# IP_12081213.net
KiCad netlist of a schematic drawn in Altium Designer
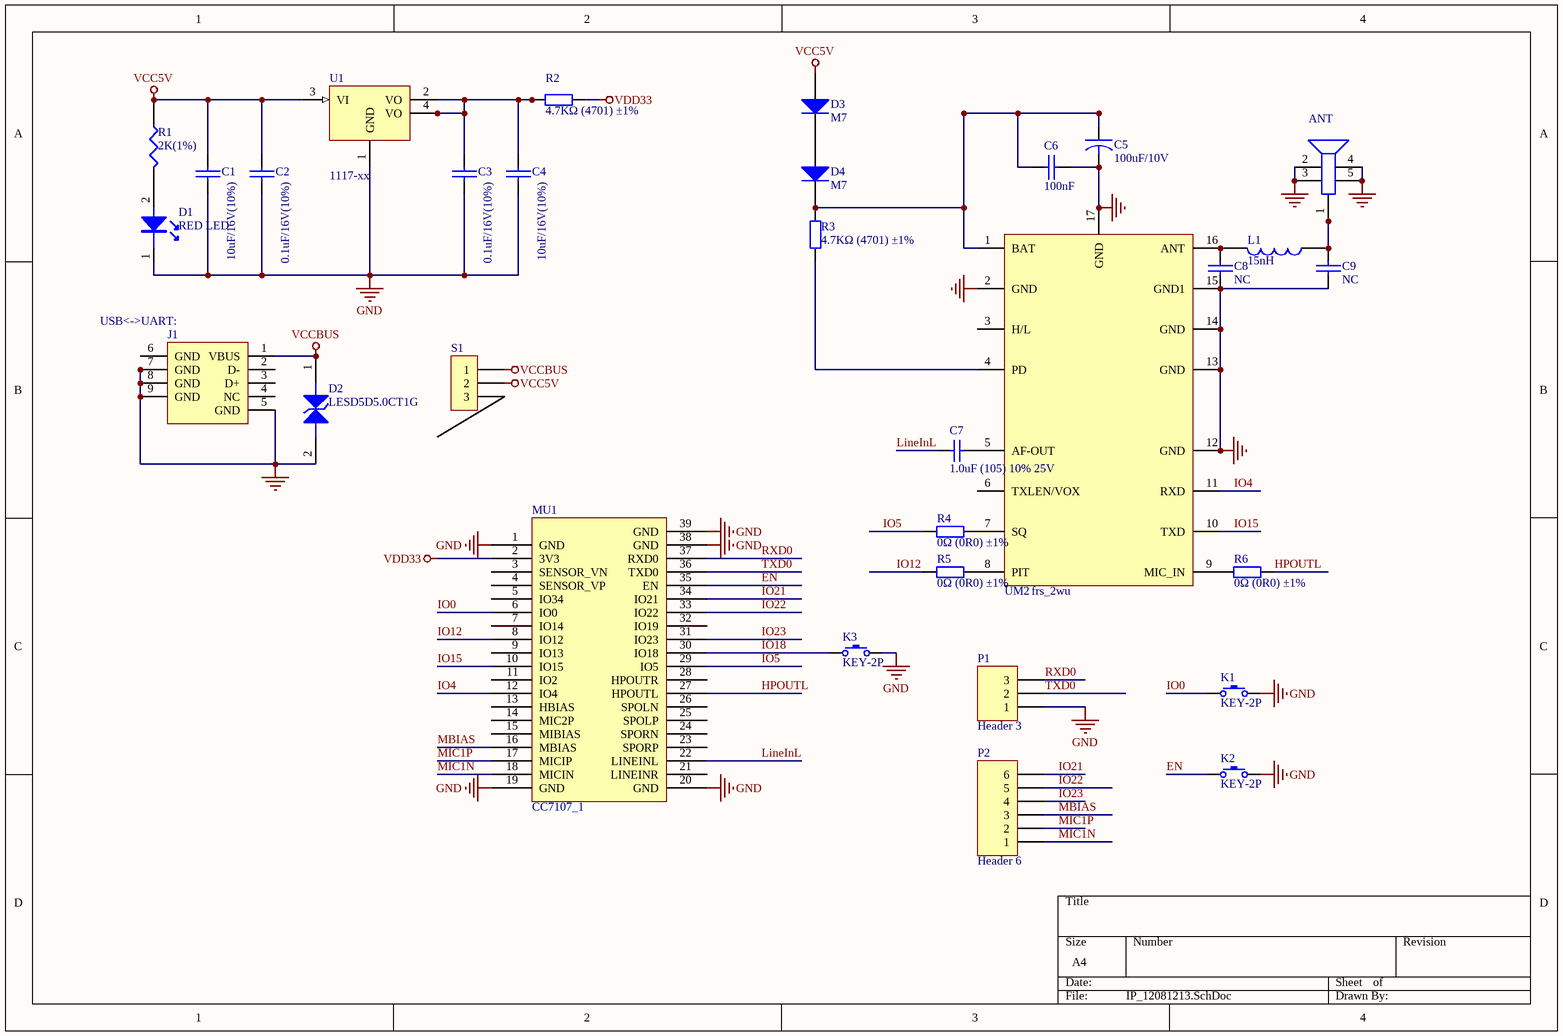
[diagram p0: IP_12081213.SchDoc]

(export (version "E")
  (design (tool "Eeschema 10.0.6"))
  (components
    (comp (ref "ANT")
      (value "~")
      (footprint "SMA-kHD信号输入头长 5.1宽5.1 5脚")
      (libsource (lib "*") (part "SPEAKER1"))
    )
    (comp (ref "C1")
      (value "10uF/16V(10%)")
      (footprint "LC-0603_C")
      (description "Capacitor")
      (libsource (lib "*") (part "CAP"))
    )
    (comp (ref "C2")
      (value "0.1uF/16V(10%)")
      (footprint "LC-0402_C")
      (description "Capacitor")
      (libsource (lib "*") (part "CAP"))
    )
    (comp (ref "C3")
      (value "0.1uF/16V(10%)")
      (footprint "LC-0402_C")
      (description "Capacitor")
      (libsource (lib "*") (part "CAP"))
    )
    (comp (ref "C4")
      (value "10uF/16V(10%)")
      (footprint "LC-0603_C")
      (description "Capacitor")
      (libsource (lib "*") (part "CAP"))
    )
    (comp (ref "C5")
      (value "100uF/10V")
      (footprint "3216")
      (description "Capacitor")
      (libsource (lib "*") (part "CAPACITOR"))
    )
    (comp (ref "C6")
      (value "100nF")
      (footprint "LC-0402_C")
      (description "Capacitor")
      (libsource (lib "*") (part "CAP"))
    )
    (comp (ref "C7")
      (value "1.0uF (105) 10% 25V")
      (footprint "LC-0402_C")
      (description "贴片电容")
      (libsource (lib "Miscellaneous Devices LC") (part "0402 1.0uF (105) 10% 25V"))
    )
    (comp (ref "C8")
      (value "NC")
      (footprint "LC-0402_C")
      (description "Capacitor")
      (libsource (lib "*") (part "CAP"))
    )
    (comp (ref "C9")
      (value "NC")
      (footprint "LC-0402_C")
      (description "Capacitor")
      (libsource (lib "*") (part "CAP"))
    )
    (comp (ref "D1")
      (value "RED LED")
      (footprint "LED5MM 2.6 6")
      (description "LED, SMD, GREEN, 3x2.2mm")
      (libsource (lib "*") (part "LEDA"))
    )
    (comp (ref "D2")
      (value "LESD5D5.0CT1G")
      (footprint "LC-SOD-523")
      (description "Zener Diode")
      (libsource (lib "*") (part "LESD5D5.0CT1G"))
    )
    (comp (ref "D3")
      (value "M7")
      (footprint "SMA")
      (description "二极管")
      (libsource (lib "Miscellaneous Devices LC") (part "SMA(DO-214AC) M7"))
    )
    (comp (ref "D4")
      (value "M7")
      (footprint "SMA")
      (description "二极管")
      (libsource (lib "Miscellaneous Devices LC") (part "SMA(DO-214AC) M7"))
    )
    (comp (ref "J1")
      (value "~")
      (footprint "USB MICRO5P/F B型牛角 - 3D")
      (libsource (lib "*") (part "USB_CON8"))
    )
    (comp (ref "K1")
      (value "KEY-2P")
      (footprint "key - 1")
      (description "Key")
      (libsource (lib "General") (part "KEY-2P"))
    )
    (comp (ref "K2")
      (value "KEY-2P")
      (footprint "key - 1")
      (description "Key")
      (libsource (lib "General") (part "KEY-2P"))
    )
    (comp (ref "K3")
      (value "KEY-2P")
      (footprint "KE卧式带支架 6*6*4.3/5/6/7/8/9.5 2脚侧按微动")
      (description "Key")
      (libsource (lib "General") (part "KEY-2P"))
    )
    (comp (ref "L1") (value "15nH") (footprint "LC-1206_L") (libsource (lib "*") (part "INDUCTOR")))
    (comp (ref "MU1")
      (value "CC7107_1")
      (footprint "ESP32-A1S")
      (libsource (lib "SchLibl") (part "CC7107_1"))
    )
    (comp (ref "P1")
      (value "Header 3")
      (footprint "HDR1X3")
      (description "Header, 3-Pin")
      (fields (field (name "PUBLISHER") "Altium Limited"))
      (libsource (lib "Miscellaneous Connectors") (part "Header 3"))
    )
    (comp (ref "P2")
      (value "Header 6")
      (footprint "HDR1X6")
      (description "Header, 6-Pin")
      (fields (field (name "PUBLISHER") "Altium Limited"))
      (libsource (lib "Miscellaneous Connectors") (part "Header 6"))
    )
    (comp (ref "R1") (value "2K(1%)") (footprint "LC-0402_R") (libsource (lib "*") (part "RES1")))
    (comp (ref "R2")
      (value "4.7KΩ (4701) ±1%")
      (footprint "LC-0402_R")
      (description "贴片电阻")
      (libsource (lib "") (part "0402 4.7KΩ (4701) 1%_1"))
    )
    (comp (ref "R3")
      (value "4.7KΩ (4701) ±1%")
      (footprint "LC-0402_R")
      (description "贴片电阻")
      (libsource (lib "Miscellaneous Devices LC") (part "0402 4.7KΩ (4701) 1%"))
    )
    (comp (ref "R4")
      (value "0Ω (0R0) ±1%")
      (footprint "LC-0402_R")
      (description "贴片电阻")
      (libsource (lib "Miscellaneous Devices LC") (part "0402 0Ω (0R0) 1%"))
    )
    (comp (ref "R5")
      (value "0Ω (0R0) ±1%")
      (footprint "LC-0402_R")
      (description "贴片电阻")
      (libsource (lib "Miscellaneous Devices LC") (part "0402 0Ω (0R0) 1%"))
    )
    (comp (ref "R6")
      (value "0Ω (0R0) ±1%")
      (footprint "LC-0402_R")
      (description "贴片电阻")
      (libsource (lib "Miscellaneous Devices LC") (part "0402 0Ω (0R0) 1%"))
    )
    (comp (ref "S1")
      (value "~")
      (footprint "K 两档开关SS-21D00")
      (description "Connector")
      (libsource (lib "*") (part "CON3"))
    )
    (comp (ref "U1")
      (value "1117-xx")
      (footprint "SOT223 LM1117")
      (description "Linear Regulator")
      (libsource (lib "General") (part "1117"))
    )
    (comp (ref "UM2") (value "frs_2wu") (footprint "模块HKT-82-VER02") (libsource (lib "*") (part "IC")))
  )
  (nets
    (net (code "1") (name "/EN") (class "Default")
      (node (ref "K2") (pin "1") (pinfunction "1_1") (pintype "passive"))
      (node (ref "MU1") (pin "35") (pinfunction "EN_35") (pintype "passive"))
    )
    (net (code "2") (name "/HPOUTL") (class "Default")
      (node (ref "MU1") (pin "27") (pinfunction "HPOUTL_27") (pintype "passive"))
      (node (ref "R6") (pin "2") (pinfunction "2_2") (pintype "passive"))
    )
    (net (code "3") (name "/IO0") (class "Default")
      (node (ref "K1") (pin "1") (pinfunction "1_1") (pintype "passive"))
      (node (ref "MU1") (pin "6") (pinfunction "IO0_6") (pintype "passive"))
    )
    (net (code "4") (name "/IO4") (class "Default")
      (node (ref "MU1") (pin "12") (pinfunction "IO4_12") (pintype "passive"))
      (node (ref "UM2") (pin "11") (pinfunction "RXD_11") (pintype "passive"))
    )
    (net (code "5") (name "/IO5") (class "Default")
      (node (ref "MU1") (pin "29") (pinfunction "IO5_29") (pintype "passive"))
      (node (ref "R4") (pin "1") (pinfunction "1_1") (pintype "passive"))
    )
    (net (code "6") (name "/IO12") (class "Default")
      (node (ref "MU1") (pin "8") (pinfunction "IO12_8") (pintype "passive"))
      (node (ref "R5") (pin "1") (pinfunction "1_1") (pintype "passive"))
    )
    (net (code "7") (name "/IO15") (class "Default")
      (node (ref "MU1") (pin "10") (pinfunction "IO15_10") (pintype "passive"))
      (node (ref "UM2") (pin "10") (pinfunction "TXD_10") (pintype "passive"))
    )
    (net (code "8") (name "/IO18") (class "Default")
      (node (ref "K3") (pin "1") (pinfunction "1_1") (pintype "passive"))
      (node (ref "MU1") (pin "30") (pinfunction "IO18_30") (pintype "passive"))
    )
    (net (code "9") (name "/IO21") (class "Default")
      (node (ref "MU1") (pin "34") (pinfunction "IO21_34") (pintype "passive"))
      (node (ref "P2") (pin "6") (pinfunction "6_6") (pintype "passive"))
    )
    (net (code "10") (name "/IO22") (class "Default")
      (node (ref "MU1") (pin "33") (pinfunction "IO22_33") (pintype "passive"))
      (node (ref "P2") (pin "5") (pinfunction "5_5") (pintype "passive"))
    )
    (net (code "11") (name "/IO23") (class "Default")
      (node (ref "MU1") (pin "31") (pinfunction "IO23_31") (pintype "passive"))
      (node (ref "P2") (pin "4") (pinfunction "4_4") (pintype "passive"))
    )
    (net (code "12") (name "/LineInL") (class "Default")
      (node (ref "C7") (pin "1") (pinfunction "1_1") (pintype "passive"))
      (node (ref "MU1") (pin "22") (pinfunction "LINEINL_22") (pintype "passive"))
    )
    (net (code "13") (name "/MBIAS") (class "Default")
      (node (ref "MU1") (pin "16") (pinfunction "MBIAS_16") (pintype "passive"))
      (node (ref "P2") (pin "3") (pinfunction "3_3") (pintype "passive"))
    )
    (net (code "14") (name "/MIC1N") (class "Default")
      (node (ref "MU1") (pin "18") (pinfunction "MICIN_18") (pintype "passive"))
      (node (ref "P2") (pin "1") (pinfunction "1_1") (pintype "passive"))
    )
    (net (code "15") (name "/MIC1P") (class "Default")
      (node (ref "MU1") (pin "17") (pinfunction "MICIP_17") (pintype "passive"))
      (node (ref "P2") (pin "2") (pinfunction "2_2") (pintype "passive"))
    )
    (net (code "16") (name "/RXD0") (class "Default")
      (node (ref "MU1") (pin "37") (pinfunction "RXD0_37") (pintype "passive"))
      (node (ref "P1") (pin "3") (pinfunction "3_3") (pintype "passive"))
    )
    (net (code "17") (name "/TXD0") (class "Default")
      (node (ref "MU1") (pin "36") (pinfunction "TXD0_36") (pintype "passive"))
      (node (ref "P1") (pin "2") (pinfunction "2_2") (pintype "passive"))
    )
    (net (code "18") (name "GND") (class "Default")
      (node (ref "ANT") (pin "2") (pinfunction "2_2") (pintype "passive"))
      (node (ref "ANT") (pin "3") (pinfunction "3_3") (pintype "passive"))
      (node (ref "ANT") (pin "4") (pinfunction "4_4") (pintype "passive"))
      (node (ref "ANT") (pin "5") (pinfunction "5_5") (pintype "passive"))
      (node (ref "C1") (pin "2") (pinfunction "2_2") (pintype "passive"))
      (node (ref "C2") (pin "2") (pinfunction "2_2") (pintype "passive"))
      (node (ref "C3") (pin "2") (pinfunction "2_2") (pintype "passive"))
      (node (ref "C4") (pin "2") (pinfunction "2_2") (pintype "passive"))
      (node (ref "C5") (pin "2") (pinfunction "2_2") (pintype "passive"))
      (node (ref "C6") (pin "2") (pinfunction "2_2") (pintype "passive"))
      (node (ref "C8") (pin "2") (pinfunction "2_2") (pintype "passive"))
      (node (ref "C9") (pin "2") (pinfunction "2_2") (pintype "passive"))
      (node (ref "D1") (pin "1") (pinfunction "C_1") (pintype "passive"))
      (node (ref "D2") (pin "2") (pinfunction "K_2") (pintype "passive"))
      (node (ref "J1") (pin "5") (pinfunction "GND_5") (pintype "passive"))
      (node (ref "J1") (pin "7") (pinfunction "GND_7") (pintype "passive"))
      (node (ref "J1") (pin "8") (pinfunction "GND_8") (pintype "passive"))
      (node (ref "J1") (pin "9") (pinfunction "GND_9") (pintype "passive"))
      (node (ref "K1") (pin "2") (pinfunction "2_2") (pintype "passive"))
      (node (ref "K2") (pin "2") (pinfunction "2_2") (pintype "passive"))
      (node (ref "K3") (pin "2") (pinfunction "2_2") (pintype "passive"))
      (node (ref "MU1") (pin "1") (pinfunction "GND_1") (pintype "passive"))
      (node (ref "MU1") (pin "19") (pinfunction "GND_19") (pintype "passive"))
      (node (ref "MU1") (pin "20") (pinfunction "GND_20") (pintype "passive"))
      (node (ref "MU1") (pin "38") (pinfunction "GND_38") (pintype "passive"))
      (node (ref "MU1") (pin "39") (pinfunction "GND_39") (pintype "passive"))
      (node (ref "P1") (pin "1") (pinfunction "1_1") (pintype "passive"))
      (node (ref "U1") (pin "1") (pinfunction "GND_1") (pintype "power_in"))
      (node (ref "UM2") (pin "12") (pinfunction "GND_12") (pintype "passive"))
      (node (ref "UM2") (pin "13") (pinfunction "GND_13") (pintype "passive"))
      (node (ref "UM2") (pin "14") (pinfunction "GND_14") (pintype "passive"))
      (node (ref "UM2") (pin "15") (pinfunction "GND1_15") (pintype "passive"))
      (node (ref "UM2") (pin "17") (pinfunction "GND_17") (pintype "passive"))
      (node (ref "UM2") (pin "2") (pinfunction "GND_2") (pintype "passive"))
    )
    (net (code "19") (name "Net-(ANT-Pad1)") (class "Default")
      (node (ref "ANT") (pin "1") (pinfunction "1_1") (pintype "passive"))
      (node (ref "C9") (pin "1") (pinfunction "1_1") (pintype "passive"))
      (node (ref "L1") (pin "2") (pinfunction "2_2") (pintype "passive"))
    )
    (net (code "20") (name "Net-(C3-Pad1)") (class "Default")
      (node (ref "C3") (pin "1") (pinfunction "1_1") (pintype "passive"))
      (node (ref "C4") (pin "1") (pinfunction "1_1") (pintype "passive"))
      (node (ref "R2") (pin "1") (pinfunction "1_1") (pintype "passive"))
      (node (ref "U1") (pin "2") (pinfunction "VO_2") (pintype "power_in"))
      (node (ref "U1") (pin "4") (pinfunction "VO_4") (pintype "power_in"))
    )
    (net (code "21") (name "Net-(D1-A)") (class "Default")
      (node (ref "D1") (pin "2") (pinfunction "A_2") (pintype "passive"))
      (node (ref "R1") (pin "2") (pinfunction "2_2") (pintype "passive"))
    )
    (net (code "22") (name "Net-(D3-K)") (class "Default")
      (node (ref "D3") (pin "2") (pinfunction "K_2") (pintype "passive"))
      (node (ref "D4") (pin "1") (pinfunction "A_1") (pintype "passive"))
    )
    (net (code "23") (name "Net-(D4-K)") (class "Default")
      (node (ref "C5") (pin "1") (pinfunction "1_1") (pintype "passive"))
      (node (ref "C6") (pin "1") (pinfunction "1_1") (pintype "passive"))
      (node (ref "D4") (pin "2") (pinfunction "K_2") (pintype "passive"))
      (node (ref "R3") (pin "2") (pinfunction "2_2") (pintype "passive"))
      (node (ref "UM2") (pin "1") (pinfunction "BAT_1") (pintype "passive"))
    )
    (net (code "24") (name "Net-(UM2-AF-OUT)") (class "Default")
      (node (ref "C7") (pin "2") (pinfunction "2_2") (pintype "passive"))
      (node (ref "UM2") (pin "5") (pinfunction "AF-OUT_5") (pintype "passive"))
    )
    (net (code "25") (name "Net-(UM2-ANT)") (class "Default")
      (node (ref "C8") (pin "1") (pinfunction "1_1") (pintype "passive"))
      (node (ref "L1") (pin "1") (pinfunction "1_1") (pintype "passive"))
      (node (ref "UM2") (pin "16") (pinfunction "ANT_16") (pintype "passive"))
    )
    (net (code "26") (name "Net-(UM2-MIC_IN)") (class "Default")
      (node (ref "R6") (pin "1") (pinfunction "1_1") (pintype "passive"))
      (node (ref "UM2") (pin "9") (pinfunction "MIC_IN_9") (pintype "passive"))
    )
    (net (code "27") (name "Net-(UM2-PD)") (class "Default")
      (node (ref "R3") (pin "1") (pinfunction "1_1") (pintype "passive"))
      (node (ref "UM2") (pin "4") (pinfunction "PD_4") (pintype "passive"))
    )
    (net (code "28") (name "Net-(UM2-PIT)") (class "Default")
      (node (ref "R5") (pin "2") (pinfunction "2_2") (pintype "passive"))
      (node (ref "UM2") (pin "8") (pinfunction "PIT_8") (pintype "passive"))
    )
    (net (code "29") (name "Net-(UM2-SQ)") (class "Default")
      (node (ref "R4") (pin "2") (pinfunction "2_2") (pintype "passive"))
      (node (ref "UM2") (pin "7") (pinfunction "SQ_7") (pintype "passive"))
    )
    (net (code "30") (name "VCC5V") (class "Default")
      (node (ref "C1") (pin "1") (pinfunction "1_1") (pintype "passive"))
      (node (ref "C2") (pin "1") (pinfunction "1_1") (pintype "passive"))
      (node (ref "D3") (pin "1") (pinfunction "A_1") (pintype "passive"))
      (node (ref "R1") (pin "1") (pinfunction "1_1") (pintype "passive"))
      (node (ref "S1") (pin "2") (pinfunction "2_2") (pintype "passive"))
      (node (ref "U1") (pin "3") (pinfunction "VI_3") (pintype "input"))
    )
    (net (code "31") (name "VCCBUS") (class "Default")
      (node (ref "D2") (pin "1") (pinfunction "A_1") (pintype "passive"))
      (node (ref "J1") (pin "1") (pinfunction "VBUS_1") (pintype "passive"))
      (node (ref "S1") (pin "1") (pinfunction "1_1") (pintype "passive"))
    )
    (net (code "32") (name "VDD33") (class "Default")
      (node (ref "MU1") (pin "2") (pinfunction "3V3_2") (pintype "passive"))
      (node (ref "R2") (pin "2") (pinfunction "2_2") (pintype "passive"))
    )
    (net (code "33") (name "unconnected-(J1-D+-Pad3)") (class "Default")
      (node (ref "J1") (pin "3") (pinfunction "D+_3") (pintype "passive"))
    )
    (net (code "34") (name "unconnected-(J1-D--Pad2)") (class "Default")
      (node (ref "J1") (pin "2") (pinfunction "D-_2") (pintype "passive"))
    )
    (net (code "35") (name "unconnected-(J1-GND-Pad6)") (class "Default")
      (node (ref "J1") (pin "6") (pinfunction "GND_6") (pintype "passive"))
    )
    (net (code "36") (name "unconnected-(J1-NC-Pad4)") (class "Default")
      (node (ref "J1") (pin "4") (pinfunction "NC_4") (pintype "passive"))
    )
    (net (code "37") (name "unconnected-(MU1-HBIAS-Pad13)") (class "Default")
      (node (ref "MU1") (pin "13") (pinfunction "HBIAS_13") (pintype "passive"))
    )
    (net (code "38") (name "unconnected-(MU1-HPOUTR-Pad28)") (class "Default")
      (node (ref "MU1") (pin "28") (pinfunction "HPOUTR_28") (pintype "passive"))
    )
    (net (code "39") (name "unconnected-(MU1-IO2-Pad11)") (class "Default")
      (node (ref "MU1") (pin "11") (pinfunction "IO2_11") (pintype "passive"))
    )
    (net (code "40") (name "unconnected-(MU1-IO13-Pad9)") (class "Default")
      (node (ref "MU1") (pin "9") (pinfunction "IO13_9") (pintype "passive"))
    )
    (net (code "41") (name "unconnected-(MU1-IO14-Pad7)") (class "Default")
      (node (ref "MU1") (pin "7") (pinfunction "IO14_7") (pintype "passive"))
    )
    (net (code "42") (name "unconnected-(MU1-IO19-Pad32)") (class "Default")
      (node (ref "MU1") (pin "32") (pinfunction "IO19_32") (pintype "passive"))
    )
    (net (code "43") (name "unconnected-(MU1-IO34-Pad5)") (class "Default")
      (node (ref "MU1") (pin "5") (pinfunction "IO34_5") (pintype "passive"))
    )
    (net (code "44") (name "unconnected-(MU1-LINEINR-Pad21)") (class "Default")
      (node (ref "MU1") (pin "21") (pinfunction "LINEINR_21") (pintype "passive"))
    )
    (net (code "45") (name "unconnected-(MU1-MIBIAS-Pad15)") (class "Default")
      (node (ref "MU1") (pin "15") (pinfunction "MIBIAS_15") (pintype "passive"))
    )
    (net (code "46") (name "unconnected-(MU1-MIC2P-Pad14)") (class "Default")
      (node (ref "MU1") (pin "14") (pinfunction "MIC2P_14") (pintype "passive"))
    )
    (net (code "47") (name "unconnected-(MU1-SENSOR_VN-Pad3)") (class "Default")
      (node (ref "MU1") (pin "3") (pinfunction "SENSOR_VN_3") (pintype "passive"))
    )
    (net (code "48") (name "unconnected-(MU1-SENSOR_VP-Pad4)") (class "Default")
      (node (ref "MU1") (pin "4") (pinfunction "SENSOR_VP_4") (pintype "passive"))
    )
    (net (code "49") (name "unconnected-(MU1-SPOLN-Pad26)") (class "Default")
      (node (ref "MU1") (pin "26") (pinfunction "SPOLN_26") (pintype "passive"))
    )
    (net (code "50") (name "unconnected-(MU1-SPOLP-Pad25)") (class "Default")
      (node (ref "MU1") (pin "25") (pinfunction "SPOLP_25") (pintype "passive"))
    )
    (net (code "51") (name "unconnected-(MU1-SPORN-Pad24)") (class "Default")
      (node (ref "MU1") (pin "24") (pinfunction "SPORN_24") (pintype "passive"))
    )
    (net (code "52") (name "unconnected-(MU1-SPORP-Pad23)") (class "Default")
      (node (ref "MU1") (pin "23") (pinfunction "SPORP_23") (pintype "passive"))
    )
    (net (code "53") (name "unconnected-(S1-Pad3)") (class "Default")
      (node (ref "S1") (pin "3") (pinfunction "3_3") (pintype "passive"))
    )
    (net (code "54") (name "unconnected-(UM2-H{slash}L-Pad3)") (class "Default")
      (node (ref "UM2") (pin "3") (pinfunction "H/L_3") (pintype "passive"))
    )
    (net (code "55") (name "unconnected-(UM2-TXLEN{slash}VOX-Pad6)") (class "Default")
      (node (ref "UM2") (pin "6") (pinfunction "TXLEN/VOX_6") (pintype "passive"))
    )
  )
)
